# STM32_sematik.net
KiCad netlist of a schematic drawn in Altium Designer
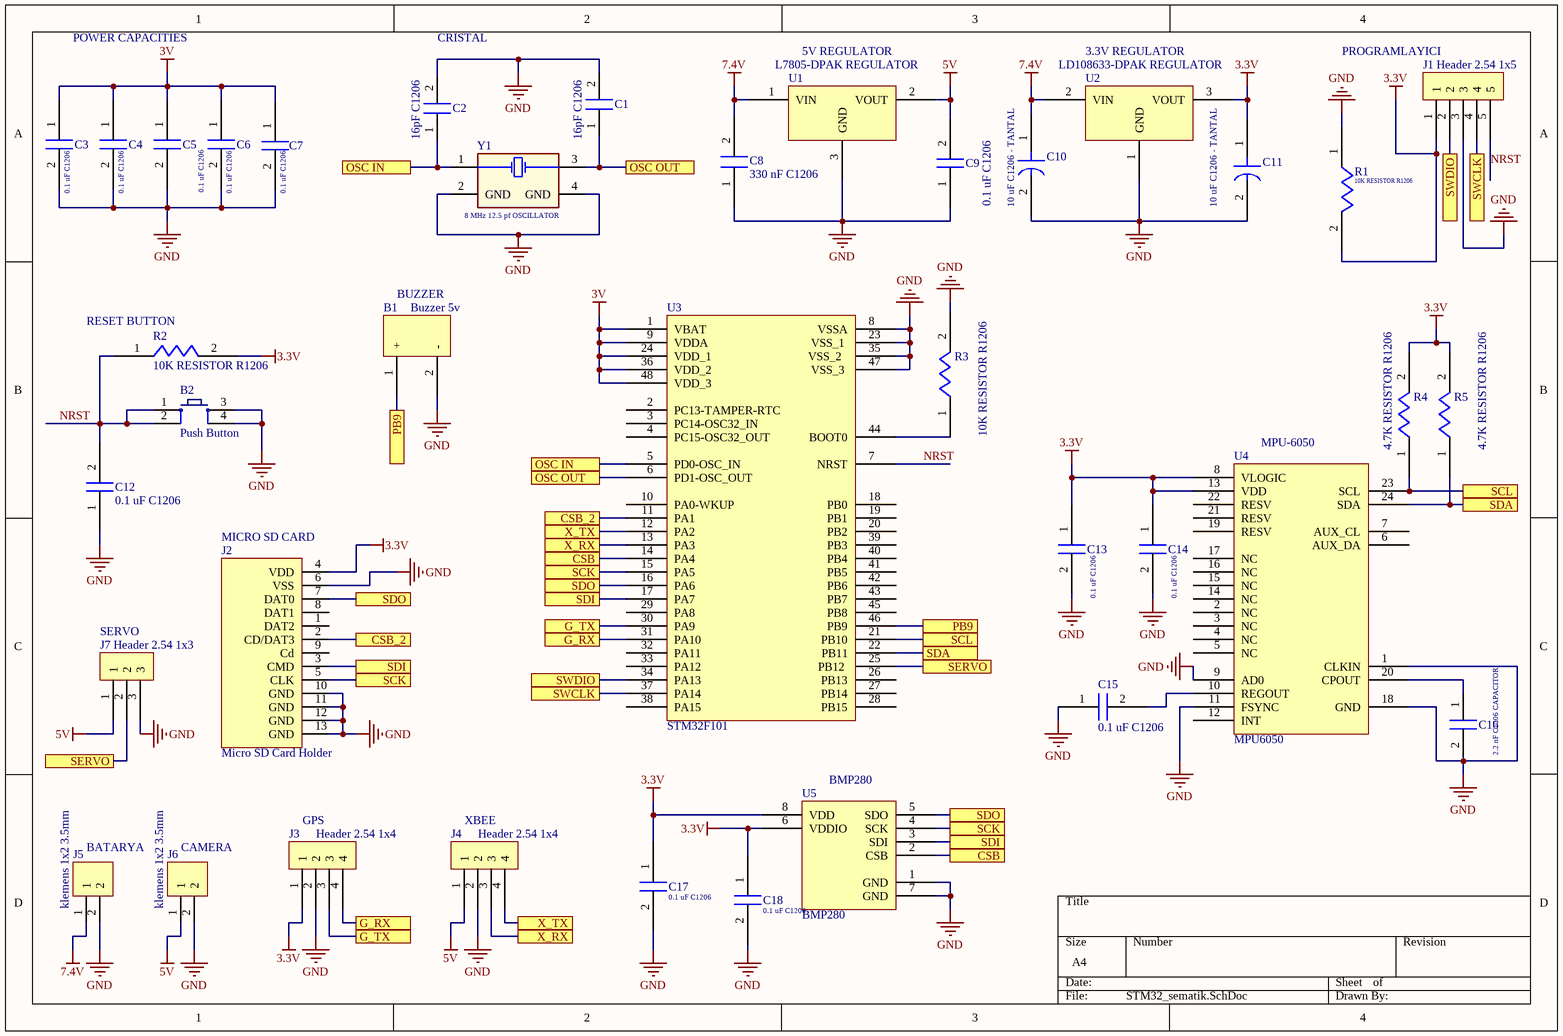
[diagram p0: STM32_sematik.SchDoc]

(export (version "E")
  (design (tool "Eeschema 10.0.6"))
  (components
    (comp (ref "B1")
      (value "Buzzer 5v")
      (footprint "Buzzer 5V")
      (libsource (lib "STM32_sematik_library") (part "Buzzer 5v"))
    )
    (comp (ref "B2")
      (value "Push Button")
      (footprint "PUSB BUTTON-SMD")
      (description "Smd Push Button")
      (libsource (lib "STM32_sematik_library") (part "Push Button"))
    )
    (comp (ref "C1")
      (value "16pF C1206")
      (footprint "C1206")
      (description "16 pF C1206")
      (libsource (lib "STM32_sematik_library") (part "16pF C1206"))
    )
    (comp (ref "C2")
      (value "16pF C1206")
      (footprint "C1206")
      (description "16 pF C1206")
      (libsource (lib "STM32_sematik_library") (part "16pF C1206"))
    )
    (comp (ref "C3")
      (value "0.1 uF C1206")
      (footprint "C1206")
      (libsource (lib "STM32_sematik_library") (part "0.1 uF C1206"))
    )
    (comp (ref "C4")
      (value "0.1 uF C1206")
      (footprint "C1206")
      (libsource (lib "STM32_sematik_library") (part "0.1 uF C1206"))
    )
    (comp (ref "C5")
      (value "0.1 uF C1206")
      (footprint "C1206")
      (libsource (lib "STM32_sematik_library") (part "0.1 uF C1206"))
    )
    (comp (ref "C6")
      (value "0.1 uF C1206")
      (footprint "C1206")
      (libsource (lib "STM32_sematik_library") (part "0.1 uF C1206"))
    )
    (comp (ref "C7")
      (value "0.1 uF C1206")
      (footprint "C1206")
      (libsource (lib "STM32_sematik_library") (part "0.1 uF C1206"))
    )
    (comp (ref "C8")
      (value "330 nF C1206")
      (footprint "C1206")
      (libsource (lib "STM32_sematik_library") (part "330 nF C1206"))
    )
    (comp (ref "C9")
      (value "0.1 uF C1206")
      (footprint "C1206")
      (libsource (lib "STM32_sematik_library") (part "0.1 uF C1206"))
    )
    (comp (ref "C10")
      (value "10 uF C1206 - TANTAL")
      (footprint "C1206 - TANTAL")
      (description "10 UF C1206 - TANTAL")
      (libsource (lib "STM32_sematik_library") (part "10 uF C1206 - TANTAL"))
    )
    (comp (ref "C11")
      (value "10 uF C1206 - TANTAL")
      (footprint "C1206 - TANTAL")
      (description "10 UF C1206 - TANTAL")
      (libsource (lib "STM32_sematik_library") (part "10 uF C1206 - TANTAL"))
    )
    (comp (ref "C12")
      (value "0.1 uF C1206")
      (footprint "C1206")
      (libsource (lib "STM32_sematik_library") (part "0.1 uF C1206"))
    )
    (comp (ref "C13")
      (value "0.1 uF C1206")
      (footprint "C1206")
      (libsource (lib "STM32_sematik_library") (part "0.1 uF C1206"))
    )
    (comp (ref "C14")
      (value "0.1 uF C1206")
      (footprint "C1206")
      (libsource (lib "STM32_sematik_library") (part "0.1 uF C1206"))
    )
    (comp (ref "C15")
      (value "0.1 uF C1206")
      (footprint "C1206")
      (libsource (lib "STM32_sematik_library") (part "0.1 uF C1206"))
    )
    (comp (ref "C16")
      (value "2.2 nF C1206 CAPACITOR")
      (footprint "C1206")
      (libsource (lib "STM32_sematik_library") (part "2.2 nF C1206 CAPACITOR"))
    )
    (comp (ref "C17")
      (value "0.1 uF C1206")
      (footprint "C1206")
      (libsource (lib "STM32_sematik_library") (part "0.1 uF C1206"))
    )
    (comp (ref "C18")
      (value "0.1 uF C1206")
      (footprint "C1206")
      (libsource (lib "STM32_sematik_library") (part "0.1 uF C1206"))
    )
    (comp (ref "J1")
      (value "Header 2.54 1x5")
      (footprint "Header 2.54 1x5")
      (libsource (lib "STM32_sematik_library") (part "Header 2.54 1x5"))
    )
    (comp (ref "J2")
      (value "Micro SD Card Holder")
      (footprint "Micro SD Card Holder")
      (libsource (lib "STM32_sematik_library") (part "Micro SD Card Holder"))
    )
    (comp (ref "J3")
      (value "Header 2.54 1x4")
      (footprint "Header 2.54 1x4")
      (libsource (lib "STM32_sematik_library") (part "Header 2.54 1x4"))
    )
    (comp (ref "J4")
      (value "Header 2.54 1x4")
      (footprint "Header 2.54 1x4")
      (libsource (lib "STM32_sematik_library") (part "Header 2.54 1x4"))
    )
    (comp (ref "J5")
      (value "klemens 1x2 3.5mm")
      (footprint "klemens 1x2 3.5mm")
      (description "Klemens 1x2 3.5mm")
      (libsource (lib "STM32_sematik_library") (part "klemens 1x2 3.5mm"))
    )
    (comp (ref "J6")
      (value "klemens 1x2 3.5mm")
      (footprint "klemens 1x2 3.5mm")
      (description "Klemens 1x2 3.5mm")
      (libsource (lib "STM32_sematik_library") (part "klemens 1x2 3.5mm"))
    )
    (comp (ref "J7")
      (value "Header 2.54 1x3")
      (footprint "Header 2.54 1x3")
      (libsource (lib "STM32_sematik_library") (part "Header 2.54 1x3"))
    )
    (comp (ref "R1")
      (value "10K RESISTOR R1206")
      (footprint "R1206 RESISTER")
      (description "R1206 RESISTER")
      (libsource (lib "STM32_sematik_library") (part "10K RESISTOR R1206"))
    )
    (comp (ref "R2")
      (value "10K RESISTOR R1206")
      (footprint "R1206 RESISTER")
      (description "R1206 RESISTER")
      (libsource (lib "STM32_sematik_library") (part "10K RESISTOR R1206"))
    )
    (comp (ref "R3")
      (value "10K RESISTOR R1206")
      (footprint "R1206 RESISTER")
      (description "R1206 RESISTER")
      (libsource (lib "STM32_sematik_library") (part "10K RESISTOR R1206"))
    )
    (comp (ref "R4")
      (value "4.7K RESISTOR R1206")
      (footprint "R1206 RESISTER")
      (description "R1206 RESISTER")
      (libsource (lib "STM32_sematik_library") (part "4.7K RESISTOR R1206"))
    )
    (comp (ref "R5")
      (value "4.7K RESISTOR R1206")
      (footprint "R1206 RESISTER")
      (description "R1206 RESISTER")
      (libsource (lib "STM32_sematik_library") (part "4.7K RESISTOR R1206"))
    )
    (comp (ref "U1")
      (value "L7805-DPAK REGULATOR")
      (footprint "L7805 DPAK")
      (description "L7805 5V REGULATOR SMD PAKET")
      (libsource (lib "STM32_sematik_library") (part "L7805-DPAK REGULATOR"))
    )
    (comp (ref "U2")
      (value "LD108633-DPAK REGULATOR")
      (footprint "L7805 DPAK")
      (description "LD108633 3.3V REGULATOR")
      (libsource (lib "STM32_sematik_library") (part "LD108633-DPAK REGULATOR"))
    )
    (comp (ref "U3")
      (value "STM32F101")
      (footprint "LQFP48-STM")
      (description "STM32F101,48 pinli microislemci")
      (libsource (lib "STM32_sematik_library") (part "STM32F101"))
    )
    (comp (ref "U4")
      (value "MPU6050")
      (footprint "MPU6050")
      (description "MPU6050 GYRO")
      (libsource (lib "STM32_sematik_library") (part "MPU6050"))
    )
    (comp (ref "U5")
      (value "BMP280")
      (footprint "BMP280")
      (description "BMP280 SENSOR")
      (libsource (lib "STM32_sematik_library") (part "BMP280"))
    )
    (comp (ref "Y1")
      (value "8 MHz 12.5 pf OSCILLATOR")
      (footprint "8 MHZ OSCILLATOR")
      (libsource (lib "STM32_sematik_library") (part "8 MHz 12.5 pf OSCILLATOR"))
    )
  )
  (nets
    (net (code "1") (name "/CSB") (class "Default")
      (node (ref "U3") (pin "14") (pinfunction "PA4_14") (pintype "passive"))
      (node (ref "U5") (pin "2") (pinfunction "CSB_2") (pintype "passive"))
    )
    (net (code "2") (name "/CSB_2") (class "Default")
      (node (ref "J2") (pin "2") (pinfunction "CD/DAT3_2") (pintype "passive"))
      (node (ref "U3") (pin "11") (pinfunction "PA1_11") (pintype "passive"))
    )
    (net (code "3") (name "/G_RX") (class "Default")
      (node (ref "J3") (pin "4") (pinfunction "4_4") (pintype "passive"))
      (node (ref "U3") (pin "31") (pinfunction "PA10_31") (pintype "passive"))
    )
    (net (code "4") (name "/G_TX") (class "Default")
      (node (ref "J3") (pin "3") (pinfunction "3_3") (pintype "passive"))
      (node (ref "U3") (pin "30") (pinfunction "PA9_30") (pintype "passive"))
    )
    (net (code "5") (name "/NRST") (class "Default")
      (node (ref "B2") (pin "1") (pinfunction "1_1") (pintype "passive"))
      (node (ref "B2") (pin "2") (pinfunction "2_2") (pintype "passive"))
      (node (ref "C12") (pin "2") (pinfunction "2_2") (pintype "passive"))
      (node (ref "J1") (pin "5") (pinfunction "5_5") (pintype "passive"))
      (node (ref "R2") (pin "1") (pinfunction "1_1") (pintype "passive"))
      (node (ref "U3") (pin "7") (pinfunction "NRST_7") (pintype "passive"))
    )
    (net (code "6") (name "/OSC IN") (class "Default")
      (node (ref "C2") (pin "1") (pinfunction "1_1") (pintype "passive"))
      (node (ref "U3") (pin "5") (pinfunction "PD0-OSC_IN_5") (pintype "passive"))
      (node (ref "Y1") (pin "1") (pintype "power_in"))
    )
    (net (code "7") (name "/OSC OUT") (class "Default")
      (node (ref "C1") (pin "1") (pinfunction "1_1") (pintype "passive"))
      (node (ref "U3") (pin "6") (pinfunction "PD1-OSC_OUT_6") (pintype "passive"))
      (node (ref "Y1") (pin "3") (pintype "passive"))
    )
    (net (code "8") (name "/PB9") (class "Default")
      (node (ref "B1") (pin "1") (pinfunction "+_1") (pintype "passive"))
      (node (ref "U3") (pin "46") (pinfunction "PB9_46") (pintype "passive"))
    )
    (net (code "9") (name "/SCK") (class "Default")
      (node (ref "J2") (pin "5") (pinfunction "CLK_5") (pintype "passive"))
      (node (ref "U3") (pin "15") (pinfunction "PA5_15") (pintype "passive"))
      (node (ref "U5") (pin "4") (pinfunction "SCK_4") (pintype "passive"))
    )
    (net (code "10") (name "/SCL") (class "Default")
      (node (ref "R4") (pin "1") (pinfunction "1_1") (pintype "passive"))
      (node (ref "U3") (pin "21") (pinfunction "PB10_21") (pintype "passive"))
      (node (ref "U4") (pin "23") (pinfunction "SCL_23") (pintype "passive"))
    )
    (net (code "11") (name "/SDA") (class "Default")
      (node (ref "R5") (pin "1") (pinfunction "1_1") (pintype "passive"))
      (node (ref "U3") (pin "22") (pinfunction "PB11_22") (pintype "passive"))
      (node (ref "U4") (pin "24") (pinfunction "SDA_24") (pintype "passive"))
    )
    (net (code "12") (name "/SDI") (class "Default")
      (node (ref "J2") (pin "3") (pinfunction "CMD_3") (pintype "passive"))
      (node (ref "U3") (pin "17") (pinfunction "PA7_17") (pintype "passive"))
      (node (ref "U5") (pin "3") (pinfunction "SDI_3") (pintype "passive"))
    )
    (net (code "13") (name "/SDO") (class "Default")
      (node (ref "J2") (pin "7") (pinfunction "DAT0_7") (pintype "passive"))
      (node (ref "U3") (pin "16") (pinfunction "PA6_16") (pintype "passive"))
      (node (ref "U5") (pin "5") (pinfunction "SDO_5") (pintype "passive"))
    )
    (net (code "14") (name "/SERVO") (class "Default")
      (node (ref "J7") (pin "2") (pinfunction "2_2") (pintype "passive"))
      (node (ref "U3") (pin "25") (pinfunction "PB12_25") (pintype "passive"))
    )
    (net (code "15") (name "/SWCLK") (class "Default")
      (node (ref "J1") (pin "4") (pinfunction "4_4") (pintype "passive"))
      (node (ref "U3") (pin "37") (pinfunction "PA14_37") (pintype "passive"))
    )
    (net (code "16") (name "/SWDIO") (class "Default")
      (node (ref "J1") (pin "2") (pinfunction "2_2") (pintype "passive"))
      (node (ref "U3") (pin "34") (pinfunction "PA13_34") (pintype "passive"))
    )
    (net (code "17") (name "/X_RX") (class "Default")
      (node (ref "J4") (pin "3") (pinfunction "3_3") (pintype "passive"))
      (node (ref "U3") (pin "13") (pinfunction "PA3_13") (pintype "passive"))
    )
    (net (code "18") (name "/X_TX") (class "Default")
      (node (ref "J4") (pin "4") (pinfunction "4_4") (pintype "passive"))
      (node (ref "U3") (pin "12") (pinfunction "PA2_12") (pintype "passive"))
    )
    (net (code "19") (name "3.3V") (class "Default")
      (node (ref "C11") (pin "1") (pinfunction "1_1") (pintype "passive"))
      (node (ref "C13") (pin "1") (pinfunction "1_1") (pintype "passive"))
      (node (ref "C14") (pin "1") (pinfunction "1_1") (pintype "passive"))
      (node (ref "C17") (pin "1") (pinfunction "1_1") (pintype "passive"))
      (node (ref "C18") (pin "1") (pinfunction "1_1") (pintype "passive"))
      (node (ref "J1") (pin "1") (pinfunction "1_1") (pintype "passive"))
      (node (ref "J2") (pin "4") (pinfunction "VDD_4") (pintype "passive"))
      (node (ref "J3") (pin "1") (pinfunction "1_1") (pintype "passive"))
      (node (ref "R1") (pin "2") (pinfunction "2_2") (pintype "passive"))
      (node (ref "R2") (pin "2") (pinfunction "2_2") (pintype "passive"))
      (node (ref "R4") (pin "2") (pinfunction "2_2") (pintype "passive"))
      (node (ref "R5") (pin "2") (pinfunction "2_2") (pintype "passive"))
      (node (ref "U2") (pin "3") (pinfunction "VOUT_3") (pintype "passive"))
      (node (ref "U4") (pin "13") (pinfunction "VDD_13") (pintype "passive"))
      (node (ref "U4") (pin "8") (pinfunction "VLOGIC_8") (pintype "passive"))
      (node (ref "U5") (pin "6") (pinfunction "VDDIO_6") (pintype "passive"))
      (node (ref "U5") (pin "8") (pinfunction "VDD_8") (pintype "passive"))
    )
    (net (code "20") (name "3V") (class "Default")
      (node (ref "C3") (pin "1") (pinfunction "1_1") (pintype "passive"))
      (node (ref "C4") (pin "1") (pinfunction "1_1") (pintype "passive"))
      (node (ref "C5") (pin "1") (pinfunction "1_1") (pintype "passive"))
      (node (ref "C6") (pin "1") (pinfunction "1_1") (pintype "passive"))
      (node (ref "C7") (pin "1") (pinfunction "1_1") (pintype "passive"))
      (node (ref "U3") (pin "1") (pinfunction "VBAT_1") (pintype "passive"))
      (node (ref "U3") (pin "24") (pinfunction "VDD_1_24") (pintype "passive"))
      (node (ref "U3") (pin "36") (pinfunction "VDD_2_36") (pintype "passive"))
      (node (ref "U3") (pin "48") (pinfunction "VDD_3_48") (pintype "passive"))
      (node (ref "U3") (pin "9") (pinfunction "VDDA_9") (pintype "passive"))
    )
    (net (code "21") (name "5V") (class "Default")
      (node (ref "C9") (pin "2") (pinfunction "2_2") (pintype "passive"))
      (node (ref "J4") (pin "1") (pinfunction "1_1") (pintype "passive"))
      (node (ref "J6") (pin "1") (pinfunction "1_1") (pintype "passive"))
      (node (ref "J7") (pin "1") (pinfunction "1_1") (pintype "passive"))
      (node (ref "U1") (pin "2") (pinfunction "VOUT_2") (pintype "passive"))
    )
    (net (code "22") (name "7.4V") (class "Default")
      (node (ref "C10") (pin "1") (pinfunction "1_1") (pintype "passive"))
      (node (ref "C8") (pin "2") (pinfunction "2_2") (pintype "passive"))
      (node (ref "J5") (pin "1") (pinfunction "1_1") (pintype "passive"))
      (node (ref "U1") (pin "1") (pinfunction "VIN_1") (pintype "passive"))
      (node (ref "U2") (pin "2") (pinfunction "VIN_2") (pintype "passive"))
    )
    (net (code "23") (name "GND") (class "Default")
      (node (ref "B1") (pin "2") (pinfunction "-_2") (pintype "passive"))
      (node (ref "B2") (pin "3") (pinfunction "3_3") (pintype "passive"))
      (node (ref "B2") (pin "4") (pinfunction "4_4") (pintype "passive"))
      (node (ref "C1") (pin "2") (pinfunction "2_2") (pintype "passive"))
      (node (ref "C10") (pin "2") (pinfunction "2_2") (pintype "passive"))
      (node (ref "C11") (pin "2") (pinfunction "2_2") (pintype "passive"))
      (node (ref "C12") (pin "1") (pinfunction "1_1") (pintype "passive"))
      (node (ref "C13") (pin "2") (pinfunction "2_2") (pintype "passive"))
      (node (ref "C14") (pin "2") (pinfunction "2_2") (pintype "passive"))
      (node (ref "C15") (pin "1") (pinfunction "1_1") (pintype "passive"))
      (node (ref "C16") (pin "2") (pinfunction "2_2") (pintype "passive"))
      (node (ref "C17") (pin "2") (pinfunction "2_2") (pintype "passive"))
      (node (ref "C18") (pin "2") (pinfunction "2_2") (pintype "passive"))
      (node (ref "C2") (pin "2") (pinfunction "2_2") (pintype "passive"))
      (node (ref "C3") (pin "2") (pinfunction "2_2") (pintype "passive"))
      (node (ref "C4") (pin "2") (pinfunction "2_2") (pintype "passive"))
      (node (ref "C5") (pin "2") (pinfunction "2_2") (pintype "passive"))
      (node (ref "C6") (pin "2") (pinfunction "2_2") (pintype "passive"))
      (node (ref "C7") (pin "2") (pinfunction "2_2") (pintype "passive"))
      (node (ref "C8") (pin "1") (pinfunction "1_1") (pintype "passive"))
      (node (ref "C9") (pin "1") (pinfunction "1_1") (pintype "passive"))
      (node (ref "J1") (pin "3") (pinfunction "3_3") (pintype "passive"))
      (node (ref "J2") (pin "10") (pinfunction "GND_10") (pintype "passive"))
      (node (ref "J2") (pin "11") (pinfunction "GND_11") (pintype "passive"))
      (node (ref "J2") (pin "12") (pinfunction "GND_12") (pintype "passive"))
      (node (ref "J2") (pin "13") (pinfunction "GND_13") (pintype "passive"))
      (node (ref "J2") (pin "6") (pinfunction "VSS_6") (pintype "passive"))
      (node (ref "J3") (pin "2") (pinfunction "2_2") (pintype "passive"))
      (node (ref "J4") (pin "2") (pinfunction "2_2") (pintype "passive"))
      (node (ref "J5") (pin "2") (pinfunction "2_2") (pintype "passive"))
      (node (ref "J6") (pin "2") (pinfunction "2_2") (pintype "passive"))
      (node (ref "J7") (pin "3") (pinfunction "3_3") (pintype "passive"))
      (node (ref "R1") (pin "1") (pinfunction "1_1") (pintype "passive"))
      (node (ref "R3") (pin "2") (pinfunction "2_2") (pintype "passive"))
      (node (ref "U1") (pin "3") (pinfunction "GND_3") (pintype "passive"))
      (node (ref "U2") (pin "1") (pinfunction "GND_1") (pintype "passive"))
      (node (ref "U3") (pin "23") (pinfunction "VSS_1_23") (pintype "passive"))
      (node (ref "U3") (pin "35") (pinfunction "VSS_2_35") (pintype "passive"))
      (node (ref "U3") (pin "47") (pinfunction "VSS_3_47") (pintype "passive"))
      (node (ref "U3") (pin "8") (pinfunction "VSSA_8") (pintype "passive"))
      (node (ref "U4") (pin "1") (pinfunction "CLKIN_1") (pintype "passive"))
      (node (ref "U4") (pin "11") (pinfunction "FSYNC_11") (pintype "passive"))
      (node (ref "U4") (pin "18") (pinfunction "GND_18") (pintype "passive"))
      (node (ref "U4") (pin "9") (pinfunction "AD0_9") (pintype "passive"))
      (node (ref "U5") (pin "1") (pinfunction "GND_1") (pintype "passive"))
      (node (ref "U5") (pin "7") (pinfunction "GND_7") (pintype "passive"))
      (node (ref "Y1") (pin "2") (pinfunction "GND_2") (pintype "power_in"))
      (node (ref "Y1") (pin "4") (pinfunction "GND_4") (pintype "passive"))
    )
    (net (code "24") (name "Net-(U3-BOOT0)") (class "Default")
      (node (ref "R3") (pin "1") (pinfunction "1_1") (pintype "passive"))
      (node (ref "U3") (pin "44") (pinfunction "BOOT0_44") (pintype "passive"))
    )
    (net (code "25") (name "Net-(U4-CPOUT)") (class "Default")
      (node (ref "C16") (pin "1") (pinfunction "1_1") (pintype "passive"))
      (node (ref "U4") (pin "20") (pinfunction "CPOUT_20") (pintype "passive"))
    )
    (net (code "26") (name "Net-(U4-REGOUT)") (class "Default")
      (node (ref "C15") (pin "2") (pinfunction "2_2") (pintype "passive"))
      (node (ref "U4") (pin "10") (pinfunction "REGOUT_10") (pintype "passive"))
    )
    (net (code "27") (name "unconnected-(J2-Cd-Pad9)") (class "Default")
      (node (ref "J2") (pin "9") (pinfunction "Cd_9") (pintype "passive"))
    )
    (net (code "28") (name "unconnected-(J2-DAT1-Pad8)") (class "Default")
      (node (ref "J2") (pin "8") (pinfunction "DAT1_8") (pintype "passive"))
    )
    (net (code "29") (name "unconnected-(J2-DAT2-Pad1)") (class "Default")
      (node (ref "J2") (pin "1") (pinfunction "DAT2_1") (pintype "passive"))
    )
    (net (code "30") (name "unconnected-(U3-PA0-WKUP-Pad10)") (class "Default")
      (node (ref "U3") (pin "10") (pinfunction "PA0-WKUP_10") (pintype "passive"))
    )
    (net (code "31") (name "unconnected-(U3-PA8-Pad29)") (class "Default")
      (node (ref "U3") (pin "29") (pinfunction "PA8_29") (pintype "passive"))
    )
    (net (code "32") (name "unconnected-(U3-PA11-Pad32)") (class "Default")
      (node (ref "U3") (pin "32") (pinfunction "PA11_32") (pintype "passive"))
    )
    (net (code "33") (name "unconnected-(U3-PA12-Pad33)") (class "Default")
      (node (ref "U3") (pin "33") (pinfunction "PA12_33") (pintype "passive"))
    )
    (net (code "34") (name "unconnected-(U3-PA15-Pad38)") (class "Default")
      (node (ref "U3") (pin "38") (pinfunction "PA15_38") (pintype "passive"))
    )
    (net (code "35") (name "unconnected-(U3-PB0-Pad18)") (class "Default")
      (node (ref "U3") (pin "18") (pinfunction "PB0_18") (pintype "passive"))
    )
    (net (code "36") (name "unconnected-(U3-PB1-Pad19)") (class "Default")
      (node (ref "U3") (pin "19") (pinfunction "PB1_19") (pintype "passive"))
    )
    (net (code "37") (name "unconnected-(U3-PB2-Pad20)") (class "Default")
      (node (ref "U3") (pin "20") (pinfunction "PB2_20") (pintype "passive"))
    )
    (net (code "38") (name "unconnected-(U3-PB3-Pad39)") (class "Default")
      (node (ref "U3") (pin "39") (pinfunction "PB3_39") (pintype "passive"))
    )
    (net (code "39") (name "unconnected-(U3-PB4-Pad40)") (class "Default")
      (node (ref "U3") (pin "40") (pinfunction "PB4_40") (pintype "passive"))
    )
    (net (code "40") (name "unconnected-(U3-PB5-Pad41)") (class "Default")
      (node (ref "U3") (pin "41") (pinfunction "PB5_41") (pintype "passive"))
    )
    (net (code "41") (name "unconnected-(U3-PB6-Pad42)") (class "Default")
      (node (ref "U3") (pin "42") (pinfunction "PB6_42") (pintype "passive"))
    )
    (net (code "42") (name "unconnected-(U3-PB7-Pad43)") (class "Default")
      (node (ref "U3") (pin "43") (pinfunction "PB7_43") (pintype "passive"))
    )
    (net (code "43") (name "unconnected-(U3-PB8-Pad45)") (class "Default")
      (node (ref "U3") (pin "45") (pinfunction "PB8_45") (pintype "passive"))
    )
    (net (code "44") (name "unconnected-(U3-PB13-Pad26)") (class "Default")
      (node (ref "U3") (pin "26") (pinfunction "PB13_26") (pintype "passive"))
    )
    (net (code "45") (name "unconnected-(U3-PB14-Pad27)") (class "Default")
      (node (ref "U3") (pin "27") (pinfunction "PB14_27") (pintype "passive"))
    )
    (net (code "46") (name "unconnected-(U3-PB15-Pad28)") (class "Default")
      (node (ref "U3") (pin "28") (pinfunction "PB15_28") (pintype "passive"))
    )
    (net (code "47") (name "unconnected-(U3-PC13-TAMPER-RTC-Pad2)") (class "Default")
      (node (ref "U3") (pin "2") (pinfunction "PC13-TAMPER-RTC_2") (pintype "passive"))
    )
    (net (code "48") (name "unconnected-(U3-PC14-OSC32_IN-Pad3)") (class "Default")
      (node (ref "U3") (pin "3") (pinfunction "PC14-OSC32_IN_3") (pintype "passive"))
    )
    (net (code "49") (name "unconnected-(U3-PC15-OSC32_OUT-Pad4)") (class "Default")
      (node (ref "U3") (pin "4") (pinfunction "PC15-OSC32_OUT_4") (pintype "passive"))
    )
    (net (code "50") (name "unconnected-(U4-AUX_CL-Pad7)") (class "Default")
      (node (ref "U4") (pin "7") (pinfunction "AUX_CL_7") (pintype "passive"))
    )
    (net (code "51") (name "unconnected-(U4-AUX_DA-Pad6)") (class "Default")
      (node (ref "U4") (pin "6") (pinfunction "AUX_DA_6") (pintype "passive"))
    )
    (net (code "52") (name "unconnected-(U4-INT-Pad12)") (class "Default")
      (node (ref "U4") (pin "12") (pinfunction "INT_12") (pintype "passive"))
    )
    (net (code "53") (name "unconnected-(U4-NC-Pad2)") (class "Default")
      (node (ref "U4") (pin "2") (pinfunction "NC_2") (pintype "passive"))
    )
    (net (code "54") (name "unconnected-(U4-NC-Pad3)") (class "Default")
      (node (ref "U4") (pin "3") (pinfunction "NC_3") (pintype "passive"))
    )
    (net (code "55") (name "unconnected-(U4-NC-Pad4)") (class "Default")
      (node (ref "U4") (pin "4") (pinfunction "NC_4") (pintype "passive"))
    )
    (net (code "56") (name "unconnected-(U4-NC-Pad5)") (class "Default")
      (node (ref "U4") (pin "5") (pinfunction "NC_5") (pintype "passive"))
    )
    (net (code "57") (name "unconnected-(U4-NC-Pad14)") (class "Default")
      (node (ref "U4") (pin "14") (pinfunction "NC_14") (pintype "passive"))
    )
    (net (code "58") (name "unconnected-(U4-NC-Pad15)") (class "Default")
      (node (ref "U4") (pin "15") (pinfunction "NC_15") (pintype "passive"))
    )
    (net (code "59") (name "unconnected-(U4-NC-Pad16)") (class "Default")
      (node (ref "U4") (pin "16") (pinfunction "NC_16") (pintype "passive"))
    )
    (net (code "60") (name "unconnected-(U4-NC-Pad17)") (class "Default")
      (node (ref "U4") (pin "17") (pinfunction "NC_17") (pintype "passive"))
    )
    (net (code "61") (name "unconnected-(U4-RESV-Pad19)") (class "Default")
      (node (ref "U4") (pin "19") (pinfunction "RESV_19") (pintype "passive"))
    )
    (net (code "62") (name "unconnected-(U4-RESV-Pad21)") (class "Default")
      (node (ref "U4") (pin "21") (pinfunction "RESV_21") (pintype "passive"))
    )
    (net (code "63") (name "unconnected-(U4-RESV-Pad22)") (class "Default")
      (node (ref "U4") (pin "22") (pinfunction "RESV_22") (pintype "passive"))
    )
  )
)
